# Display.net
KiCad netlist of a schematic drawn in Altium Designer
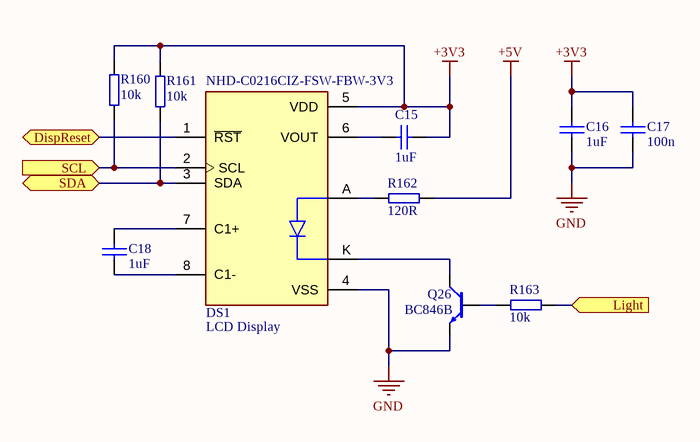
[diagram p0: Display.SchDoc]

(export (version "E")
  (design (tool "Eeschema 10.0.6"))
  (components
    (comp (ref "C15")
      (value "1uF_35V")
      (footprint "C_0603")
      (description "Capacitor [SMD]")
      (fields
        (field (name "NAME") "1uF")
        (field (name "TOLERANCE") "10%")
        (field (name "MANUFACTURER") "Murata")
      )
      (libsource (lib "PassiveBMS_schlib") (part "C_1uF_0603"))
    )
    (comp (ref "C16")
      (value "1uF_35V")
      (footprint "C_0805")
      (description "Capacitor [SMD]")
      (fields
        (field (name "NAME") "1uF")
        (field (name "TOLERANCE") "10%")
        (field (name "MANUFACTURER") "Murata")
      )
      (libsource (lib "PassiveBMS_schlib") (part "C_1uF_0805"))
    )
    (comp (ref "C17")
      (value "100nF_35V")
      (footprint "C_0805")
      (description "Capacitor [SMD]")
      (fields
        (field (name "NAME") "100n")
        (field (name "TOLERANCE") "10%")
        (field (name "MANUFACTURER") "Murata")
      )
      (libsource (lib "PassiveBMS_schlib") (part "C_100nF_0805"))
    )
    (comp (ref "C18")
      (value "1uF_35V")
      (footprint "C_0603")
      (description "Capacitor [SMD]")
      (fields
        (field (name "NAME") "1uF")
        (field (name "TOLERANCE") "10%")
        (field (name "MANUFACTURER") "Murata")
      )
      (libsource (lib "PassiveBMS_schlib") (part "C_1uF_0603"))
    )
    (comp (ref "DS1")
      (value "LCD_FSTN_Display")
      (footprint "MK_BMS_pcblib:LCD_NHD-C0216CIZ-FSW-FBW-3V3")
      (description "NHD-C0216CIZ-FSW-FBW-3V3\r\nLCD Display")
      (fields
        (field (name "MF") "Newhaven")
        (field (name "DIGI-KEY_PART_NUMBER") "NHD-C0216CIZ-FSW-FBW-3V3-ND")
        (field (name "MP") "NHD-C0216CIZ-FSW-FBW-3V3")
        (field (name "NAME") "LCD Display")
      )
      (libsource (lib "PassiveBMS_schlib") (part "LCD_FSTN_Display"))
    )
    (comp (ref "Q26")
      (value "BC846B_SOT23")
      (footprint "NPN_BJT_SOT23")
      (description "NPN transistor [SMD]")
      (fields
        (field (name "NAME") "BC846B")
        (field (name "MANUFACTURER PART NUMBER") "BC846ALT1G")
        (field (name "MANUFACTURER") "ON Semiconductor")
      )
      (libsource (lib "PassiveBMS_schlib") (part "BC846B_SOT23"))
    )
    (comp (ref "R160")
      (value "10k_125mW")
      (footprint "R_0805")
      (description "Resistor [SMD]")
      (fields
        (field (name "NAME") "10k")
        (field (name "TOLERANCE") "1%")
        (field (name "MANUFACTURER") "Vishay")
      )
      (libsource (lib "PassiveBMS_schlib") (part "R_10k_0805"))
    )
    (comp (ref "R161")
      (value "10k_125mW")
      (footprint "R_0805")
      (description "Resistor [SMD]")
      (fields
        (field (name "NAME") "10k")
        (field (name "TOLERANCE") "1%")
        (field (name "MANUFACTURER") "Vishay")
      )
      (libsource (lib "PassiveBMS_schlib") (part "R_10k_0805"))
    )
    (comp (ref "R162")
      (value "120R_125mW")
      (footprint "R_0805")
      (description "Resistor [SMD]")
      (fields
        (field (name "NAME") "120R")
        (field (name "TOLERANCE") "1%")
        (field (name "MANUFACTURER") "Vishay")
      )
      (libsource (lib "PassiveBMS_schlib") (part "R_120R_0805"))
    )
    (comp (ref "R163")
      (value "10k_125mW")
      (footprint "R_0805")
      (description "Resistor [SMD]")
      (fields
        (field (name "NAME") "10k")
        (field (name "TOLERANCE") "1%")
        (field (name "MANUFACTURER") "Vishay")
      )
      (libsource (lib "PassiveBMS_schlib") (part "R_10k_0805"))
    )
  )
  (nets
    (net (code "1") (name "+3V3") (class "Default")
      (node (ref "C15") (pin "2") (pinfunction "2_2") (pintype "passive"))
      (node (ref "C16") (pin "2") (pinfunction "2_2") (pintype "passive"))
      (node (ref "C17") (pin "2") (pinfunction "2_2") (pintype "passive"))
      (node (ref "DS1") (pin "5") (pinfunction "VDD_5") (pintype "power_in"))
      (node (ref "R160") (pin "1") (pinfunction "1_1") (pintype "passive"))
      (node (ref "R161") (pin "1") (pinfunction "1_1") (pintype "passive"))
    )
    (net (code "2") (name "+5V") (class "Default")
      (node (ref "R162") (pin "1") (pinfunction "1_1") (pintype "passive"))
    )
    (net (code "3") (name "/DispReset") (class "Default")
      (node (ref "DS1") (pin "1") (pinfunction "~{RST}_1") (pintype "passive"))
    )
    (net (code "4") (name "/Light") (class "Default")
      (node (ref "R163") (pin "1") (pinfunction "1_1") (pintype "passive"))
    )
    (net (code "5") (name "/SCL") (class "Default")
      (node (ref "DS1") (pin "2") (pinfunction "SCL_2") (pintype "passive"))
      (node (ref "R160") (pin "2") (pinfunction "2_2") (pintype "passive"))
    )
    (net (code "6") (name "/SDA") (class "Default")
      (node (ref "DS1") (pin "3") (pinfunction "SDA_3") (pintype "passive"))
      (node (ref "R161") (pin "2") (pinfunction "2_2") (pintype "passive"))
    )
    (net (code "7") (name "GND") (class "Default")
      (node (ref "C16") (pin "1") (pinfunction "1_1") (pintype "passive"))
      (node (ref "C17") (pin "1") (pinfunction "1_1") (pintype "passive"))
      (node (ref "DS1") (pin "4") (pinfunction "VSS_4") (pintype "power_in"))
      (node (ref "Q26") (pin "3") (pinfunction "E_3") (pintype "passive"))
    )
    (net (code "8") (name "Net-(DS1-C1+)") (class "Default")
      (node (ref "C18") (pin "2") (pinfunction "2_2") (pintype "passive"))
      (node (ref "DS1") (pin "7") (pinfunction "C1+_7") (pintype "passive"))
    )
    (net (code "9") (name "Net-(DS1-C1-)") (class "Default")
      (node (ref "C18") (pin "1") (pinfunction "1_1") (pintype "passive"))
      (node (ref "DS1") (pin "8") (pinfunction "C1-_8") (pintype "passive"))
    )
    (net (code "10") (name "Net-(DS1-PadA)") (class "Default")
      (node (ref "DS1") (pin "A") (pinfunction "A_A") (pintype "passive"))
      (node (ref "R162") (pin "2") (pinfunction "2_2") (pintype "passive"))
    )
    (net (code "11") (name "Net-(DS1-VOUT)") (class "Default")
      (node (ref "C15") (pin "1") (pinfunction "1_1") (pintype "passive"))
      (node (ref "DS1") (pin "6") (pinfunction "VOUT_6") (pintype "passive"))
    )
    (net (code "12") (name "Net-(Q26-B)") (class "Default")
      (node (ref "Q26") (pin "2") (pinfunction "B_2") (pintype "passive"))
      (node (ref "R163") (pin "2") (pinfunction "2_2") (pintype "passive"))
    )
    (net (code "13") (name "Net-(Q26-C)") (class "Default")
      (node (ref "DS1") (pin "K") (pinfunction "K_K") (pintype "passive"))
      (node (ref "Q26") (pin "1") (pinfunction "C_1") (pintype "passive"))
    )
  )
)
